# grbl_shield.net
KiCad netlist of a schematic drawn in EAGLE
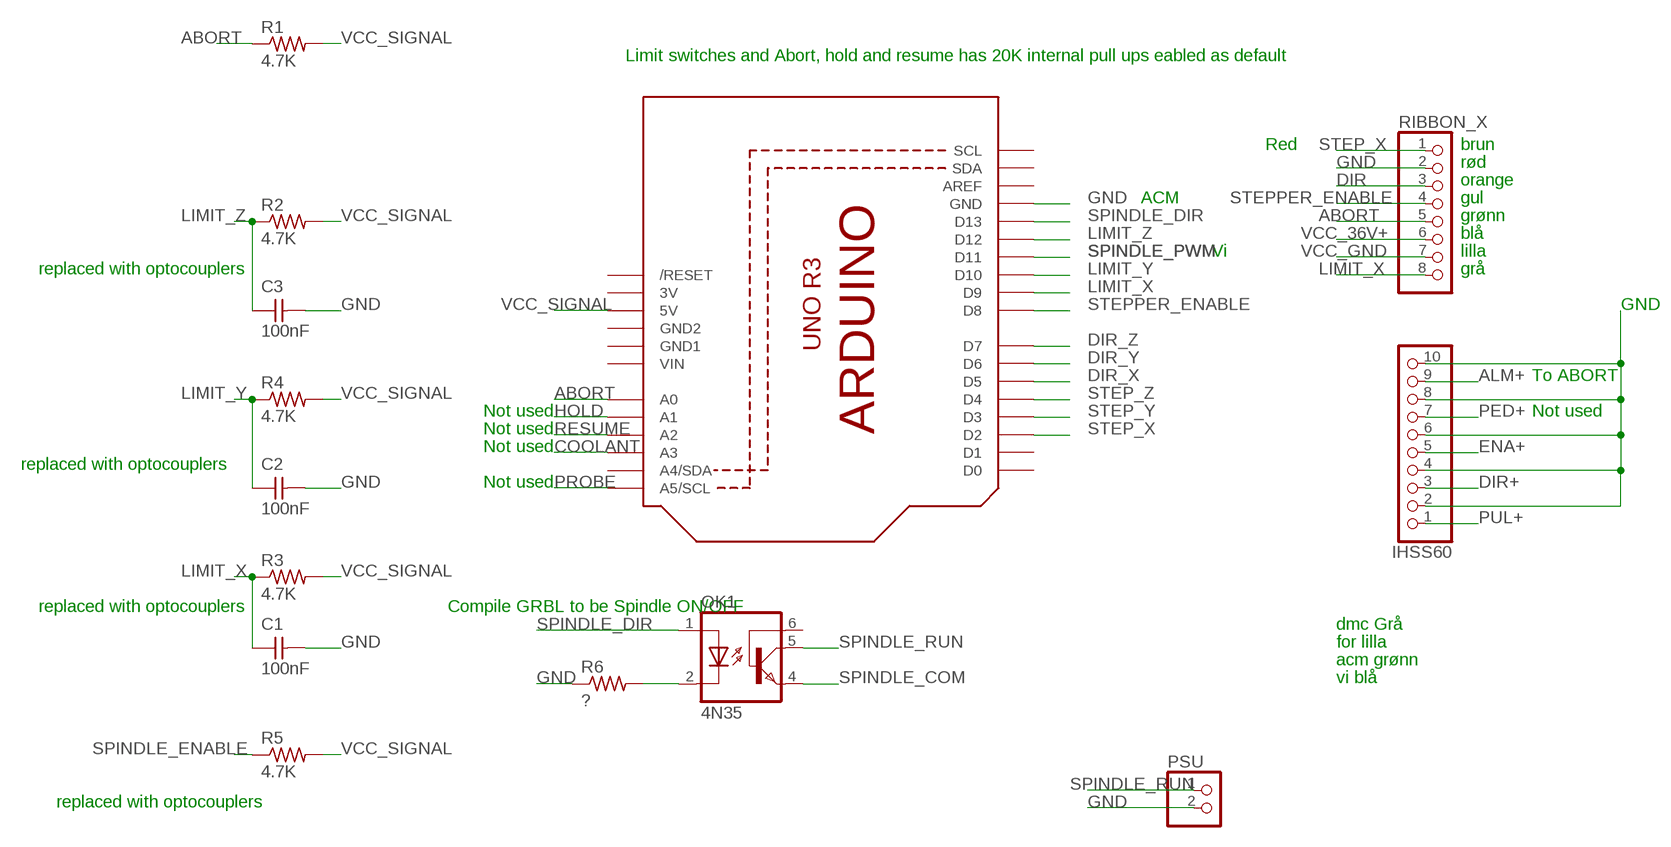
[diagram p0: schematic, sheet 1]

(export (version "E")
  (design (tool "Eeschema 10.0.6"))
  (components
    (comp (ref "C1")
      (value "100nF")
      (footprint "eagle-import:C1206FAB")
      (libsource (lib "eagle-import") (part "CAP-UNPOLARIZEDFAB"))
    )
    (comp (ref "C2")
      (value "100nF")
      (footprint "eagle-import:C1206FAB")
      (libsource (lib "eagle-import") (part "CAP-UNPOLARIZEDFAB"))
    )
    (comp (ref "C3")
      (value "100nF")
      (footprint "eagle-import:C1206FAB")
      (libsource (lib "eagle-import") (part "CAP-UNPOLARIZEDFAB"))
    )
    (comp (ref "IHSS60")
      (value "PINHD-1X10")
      (footprint "eagle-import:1X10")
      (libsource (lib "eagle-import") (part "PINHD-1X10"))
    )
    (comp (ref "OK1")
      (value "4N35")
      (footprint "eagle-import:DIL06")
      (libsource (lib "eagle-import") (part "4N35"))
    )
    (comp (ref "PSU")
      (value "PINHD-1X2")
      (footprint "eagle-import:1X02")
      (libsource (lib "eagle-import") (part "PINHD-1X2"))
    )
    (comp (ref "Q1")
      (value "ARDUINOR3-NOIOREF-NOTEXT")
      (footprint "eagle-import:ARDUINOR3-NOTEXT-NOIOREF")
      (libsource (lib "eagle-import") (part "ARDUINOR3-NOIOREF-NOTEXT"))
    )
    (comp (ref "R1")
      (value "4.7K")
      (footprint "eagle-import:R1206FAB")
      (libsource (lib "eagle-import") (part "RES-US1206FAB"))
    )
    (comp (ref "R2")
      (value "4.7K")
      (footprint "eagle-import:R1206FAB")
      (libsource (lib "eagle-import") (part "RES-US1206FAB"))
    )
    (comp (ref "R3")
      (value "4.7K")
      (footprint "eagle-import:R1206FAB")
      (libsource (lib "eagle-import") (part "RES-US1206FAB"))
    )
    (comp (ref "R4")
      (value "4.7K")
      (footprint "eagle-import:R1206FAB")
      (libsource (lib "eagle-import") (part "RES-US1206FAB"))
    )
    (comp (ref "R5")
      (value "4.7K")
      (footprint "eagle-import:R1206FAB")
      (libsource (lib "eagle-import") (part "RES-US1206FAB"))
    )
    (comp (ref "R6")
      (value "?")
      (footprint "eagle-import:R1206FAB")
      (libsource (lib "eagle-import") (part "RES-US1206FAB"))
    )
    (comp (ref "RIBBON_X")
      (value "PINHD-1X8")
      (footprint "eagle-import:1X08")
      (libsource (lib "eagle-import") (part "PINHD-1X8"))
    )
  )
  (nets
    (net (code "1") (name "/3V") (class "Default")
      (node (ref "Q1") (pin "3V") (pinfunction "3V_3V") (pintype "power_in"))
    )
    (net (code "2") (name "/ABORT") (class "Default")
      (node (ref "Q1") (pin "A0") (pinfunction "A0_A0") (pintype "bidirectional"))
      (node (ref "R1") (pin "1") (pinfunction "1_1") (pintype "passive"))
      (node (ref "RIBBON_X") (pin "5") (pinfunction "5_5") (pintype "passive"))
    )
    (net (code "3") (name "/ALM+") (class "Default")
      (node (ref "IHSS60") (pin "9") (pinfunction "9_9") (pintype "passive"))
    )
    (net (code "4") (name "/COOLANT") (class "Default")
      (node (ref "Q1") (pin "A3") (pinfunction "A3_A3") (pintype "bidirectional"))
    )
    (net (code "5") (name "/DIR") (class "Default")
      (node (ref "RIBBON_X") (pin "3") (pinfunction "3_3") (pintype "passive"))
    )
    (net (code "6") (name "/DIR+") (class "Default")
      (node (ref "IHSS60") (pin "3") (pinfunction "3_3") (pintype "passive"))
    )
    (net (code "7") (name "/DIR_X") (class "Default")
      (node (ref "Q1") (pin "D5") (pinfunction "D5_D5") (pintype "bidirectional"))
    )
    (net (code "8") (name "/DIR_Y") (class "Default")
      (node (ref "Q1") (pin "D6") (pinfunction "D6_D6") (pintype "bidirectional"))
    )
    (net (code "9") (name "/DIR_Z") (class "Default")
      (node (ref "Q1") (pin "D7") (pinfunction "D7_D7") (pintype "bidirectional"))
    )
    (net (code "10") (name "/ENA+") (class "Default")
      (node (ref "IHSS60") (pin "5") (pinfunction "5_5") (pintype "passive"))
    )
    (net (code "11") (name "/GND") (class "Default")
      (node (ref "C1") (pin "2") (pinfunction "2_2") (pintype "passive"))
      (node (ref "C2") (pin "2") (pinfunction "2_2") (pintype "passive"))
      (node (ref "C3") (pin "2") (pinfunction "2_2") (pintype "passive"))
      (node (ref "PSU") (pin "2") (pinfunction "2_2") (pintype "passive"))
      (node (ref "Q1") (pin "GND") (pinfunction "GND_GND") (pintype "power_in"))
      (node (ref "R6") (pin "1") (pinfunction "1_1") (pintype "passive"))
      (node (ref "RIBBON_X") (pin "2") (pinfunction "2_2") (pintype "passive"))
    )
    (net (code "12") (name "/GND1") (class "Default")
      (node (ref "Q1") (pin "GND1") (pinfunction "GND1_GND1") (pintype "power_in"))
    )
    (net (code "13") (name "/GND2") (class "Default")
      (node (ref "Q1") (pin "GND2") (pinfunction "GND2_GND2") (pintype "power_in"))
    )
    (net (code "14") (name "/HOLD") (class "Default")
      (node (ref "Q1") (pin "A1") (pinfunction "A1_A1") (pintype "bidirectional"))
    )
    (net (code "15") (name "/LIMIT_X") (class "Default")
      (node (ref "C1") (pin "1") (pinfunction "1_1") (pintype "passive"))
      (node (ref "Q1") (pin "D9") (pinfunction "D9_D9") (pintype "bidirectional"))
      (node (ref "R3") (pin "1") (pinfunction "1_1") (pintype "passive"))
      (node (ref "RIBBON_X") (pin "8") (pinfunction "8_8") (pintype "passive"))
    )
    (net (code "16") (name "/LIMIT_Y") (class "Default")
      (node (ref "C2") (pin "1") (pinfunction "1_1") (pintype "passive"))
      (node (ref "Q1") (pin "D10") (pinfunction "D10_D10") (pintype "bidirectional"))
      (node (ref "R4") (pin "1") (pinfunction "1_1") (pintype "passive"))
    )
    (net (code "17") (name "/LIMIT_Z") (class "Default")
      (node (ref "C3") (pin "1") (pinfunction "1_1") (pintype "passive"))
      (node (ref "Q1") (pin "D12") (pinfunction "D12_D12") (pintype "bidirectional"))
      (node (ref "R2") (pin "1") (pinfunction "1_1") (pintype "passive"))
    )
    (net (code "18") (name "/PED+") (class "Default")
      (node (ref "IHSS60") (pin "7") (pinfunction "7_7") (pintype "passive"))
    )
    (net (code "19") (name "/PROBE") (class "Default")
      (node (ref "Q1") (pin "A5") (pinfunction "A5/SCL_A5") (pintype "bidirectional"))
    )
    (net (code "20") (name "/PUL+") (class "Default")
      (node (ref "IHSS60") (pin "1") (pinfunction "1_1") (pintype "passive"))
    )
    (net (code "21") (name "/RESUME") (class "Default")
      (node (ref "Q1") (pin "A2") (pinfunction "A2_A2") (pintype "bidirectional"))
    )
    (net (code "22") (name "/SPINDLE_COM") (class "Default")
      (node (ref "OK1") (pin "4") (pinfunction "EMI_4") (pintype "passive"))
    )
    (net (code "23") (name "/SPINDLE_DIR") (class "Default")
      (node (ref "OK1") (pin "1") (pinfunction "A_1") (pintype "passive"))
      (node (ref "Q1") (pin "D13") (pinfunction "D13_D13") (pintype "bidirectional"))
    )
    (net (code "24") (name "/SPINDLE_ENABLE") (class "Default")
      (node (ref "R5") (pin "1") (pinfunction "1_1") (pintype "passive"))
    )
    (net (code "25") (name "/SPINDLE_PWM") (class "Default")
      (node (ref "Q1") (pin "D11") (pinfunction "D11_D11") (pintype "bidirectional"))
    )
    (net (code "26") (name "/SPINDLE_RUN") (class "Default")
      (node (ref "OK1") (pin "5") (pinfunction "COL_5") (pintype "passive"))
      (node (ref "PSU") (pin "1") (pinfunction "1_1") (pintype "passive"))
    )
    (net (code "27") (name "/STEPPER_ENABLE") (class "Default")
      (node (ref "Q1") (pin "D8") (pinfunction "D8_D8") (pintype "bidirectional"))
      (node (ref "RIBBON_X") (pin "4") (pinfunction "4_4") (pintype "passive"))
    )
    (net (code "28") (name "/STEP_X") (class "Default")
      (node (ref "Q1") (pin "D2") (pinfunction "D2_D2") (pintype "bidirectional"))
      (node (ref "RIBBON_X") (pin "1") (pinfunction "1_1") (pintype "passive"))
    )
    (net (code "29") (name "/STEP_Y") (class "Default")
      (node (ref "Q1") (pin "D3") (pinfunction "D3_D3") (pintype "bidirectional"))
    )
    (net (code "30") (name "/STEP_Z") (class "Default")
      (node (ref "Q1") (pin "D4") (pinfunction "D4_D4") (pintype "bidirectional"))
    )
    (net (code "31") (name "/VCC_36V+") (class "Default")
      (node (ref "RIBBON_X") (pin "6") (pinfunction "6_6") (pintype "passive"))
    )
    (net (code "32") (name "/VCC_GND") (class "Default")
      (node (ref "RIBBON_X") (pin "7") (pinfunction "7_7") (pintype "passive"))
    )
    (net (code "33") (name "/VCC_SIGNAL") (class "Default")
      (node (ref "Q1") (pin "5V") (pinfunction "5V_5V") (pintype "power_in"))
      (node (ref "R1") (pin "2") (pinfunction "2_2") (pintype "passive"))
      (node (ref "R2") (pin "2") (pinfunction "2_2") (pintype "passive"))
      (node (ref "R3") (pin "2") (pinfunction "2_2") (pintype "passive"))
      (node (ref "R4") (pin "2") (pinfunction "2_2") (pintype "passive"))
      (node (ref "R5") (pin "2") (pinfunction "2_2") (pintype "passive"))
    )
    (net (code "34") (name "/VIN") (class "Default")
      (node (ref "Q1") (pin "VIN") (pinfunction "VIN_VIN") (pintype "power_in"))
    )
    (net (code "35") (name "Net-(IHSS60-Pad10)") (class "Default")
      (node (ref "IHSS60") (pin "10") (pinfunction "10_10") (pintype "passive"))
      (node (ref "IHSS60") (pin "2") (pinfunction "2_2") (pintype "passive"))
      (node (ref "IHSS60") (pin "4") (pinfunction "4_4") (pintype "passive"))
      (node (ref "IHSS60") (pin "6") (pinfunction "6_6") (pintype "passive"))
      (node (ref "IHSS60") (pin "8") (pinfunction "8_8") (pintype "passive"))
    )
    (net (code "36") (name "Net-(OK1-C)") (class "Default")
      (node (ref "OK1") (pin "2") (pinfunction "C_2") (pintype "passive"))
      (node (ref "R6") (pin "2") (pinfunction "2_2") (pintype "passive"))
    )
    (net (code "37") (name "unconnected-(OK1-BAS-Pad6)") (class "Default")
      (node (ref "OK1") (pin "6") (pinfunction "BAS_6") (pintype "passive"))
    )
    (net (code "38") (name "unconnected-(Q1-A4{slash}SDA-PadA4)") (class "Default")
      (node (ref "Q1") (pin "A4") (pinfunction "A4/SDA_A4") (pintype "bidirectional"))
    )
    (net (code "39") (name "unconnected-(Q1-PadAREF)") (class "Default")
      (node (ref "Q1") (pin "AREF") (pinfunction "AREF_AREF") (pintype "bidirectional"))
    )
    (net (code "40") (name "unconnected-(Q1-PadD0)") (class "Default")
      (node (ref "Q1") (pin "D0") (pinfunction "D0_D0") (pintype "bidirectional"))
    )
    (net (code "41") (name "unconnected-(Q1-PadD1)") (class "Default")
      (node (ref "Q1") (pin "D1") (pinfunction "D1_D1") (pintype "bidirectional"))
    )
    (net (code "42") (name "unconnected-(Q1-PadSCL)") (class "Default")
      (node (ref "Q1") (pin "SCL") (pinfunction "SCL_SCL") (pintype "bidirectional"))
    )
    (net (code "43") (name "unconnected-(Q1-PadSDA)") (class "Default")
      (node (ref "Q1") (pin "SDA") (pinfunction "SDA_SDA") (pintype "bidirectional"))
    )
    (net (code "44") (name "unconnected-(Q1-{slash}RESET-PadRESET)") (class "Default")
      (node (ref "Q1") (pin "RESET") (pinfunction "/RESET_RESET") (pintype "bidirectional"))
    )
  )
)
